# SMC_FrontPanel_ExtensionBoard_Step2_V14_.net
KiCad netlist of a schematic drawn in EAGLE
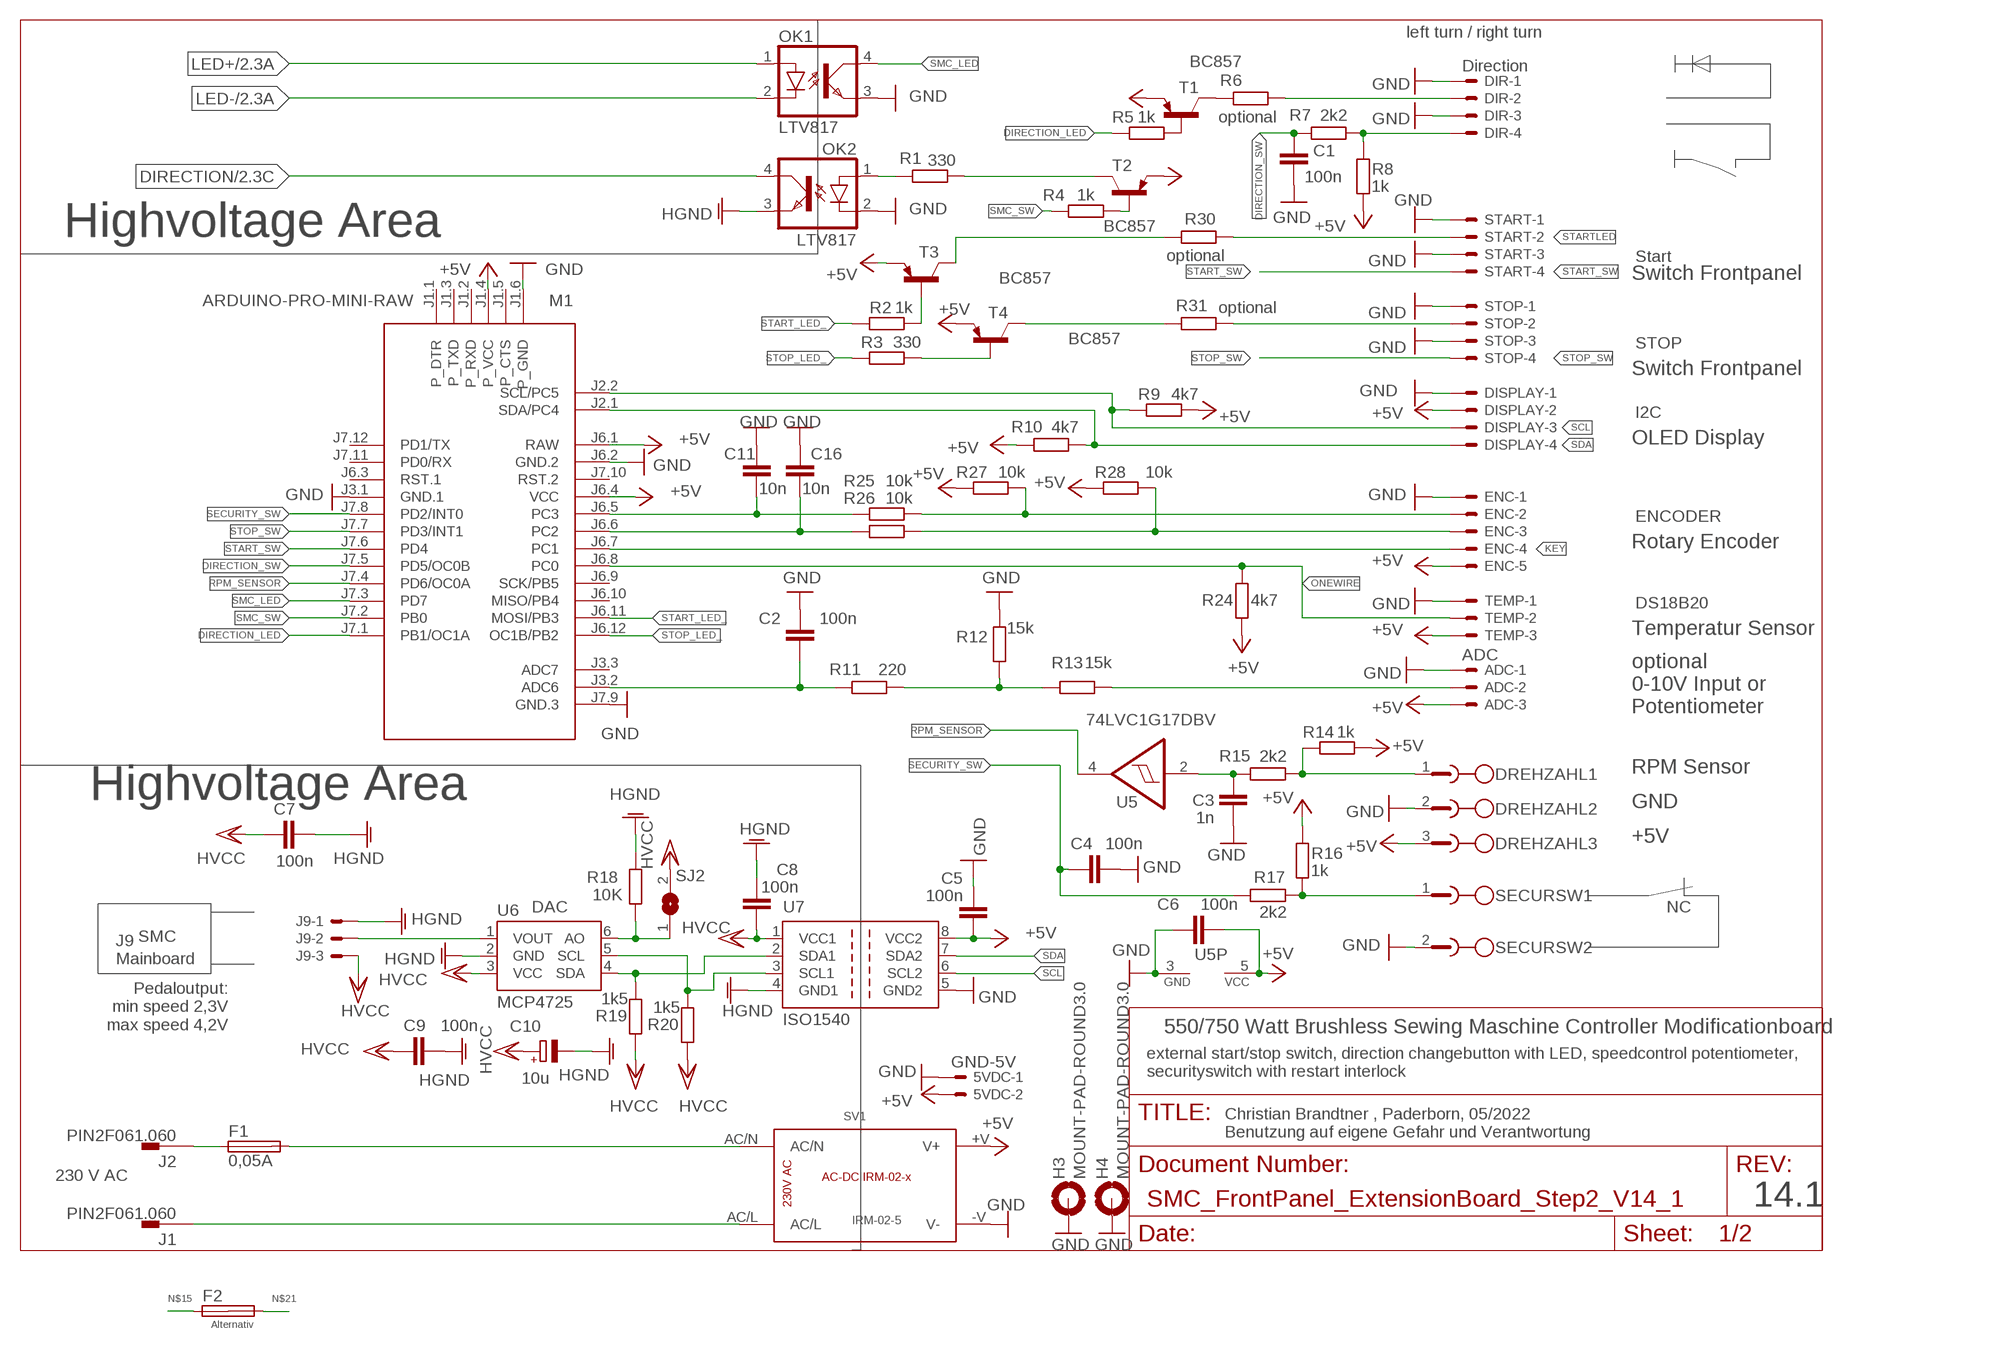
[diagram p0: schematic, sheet 1]
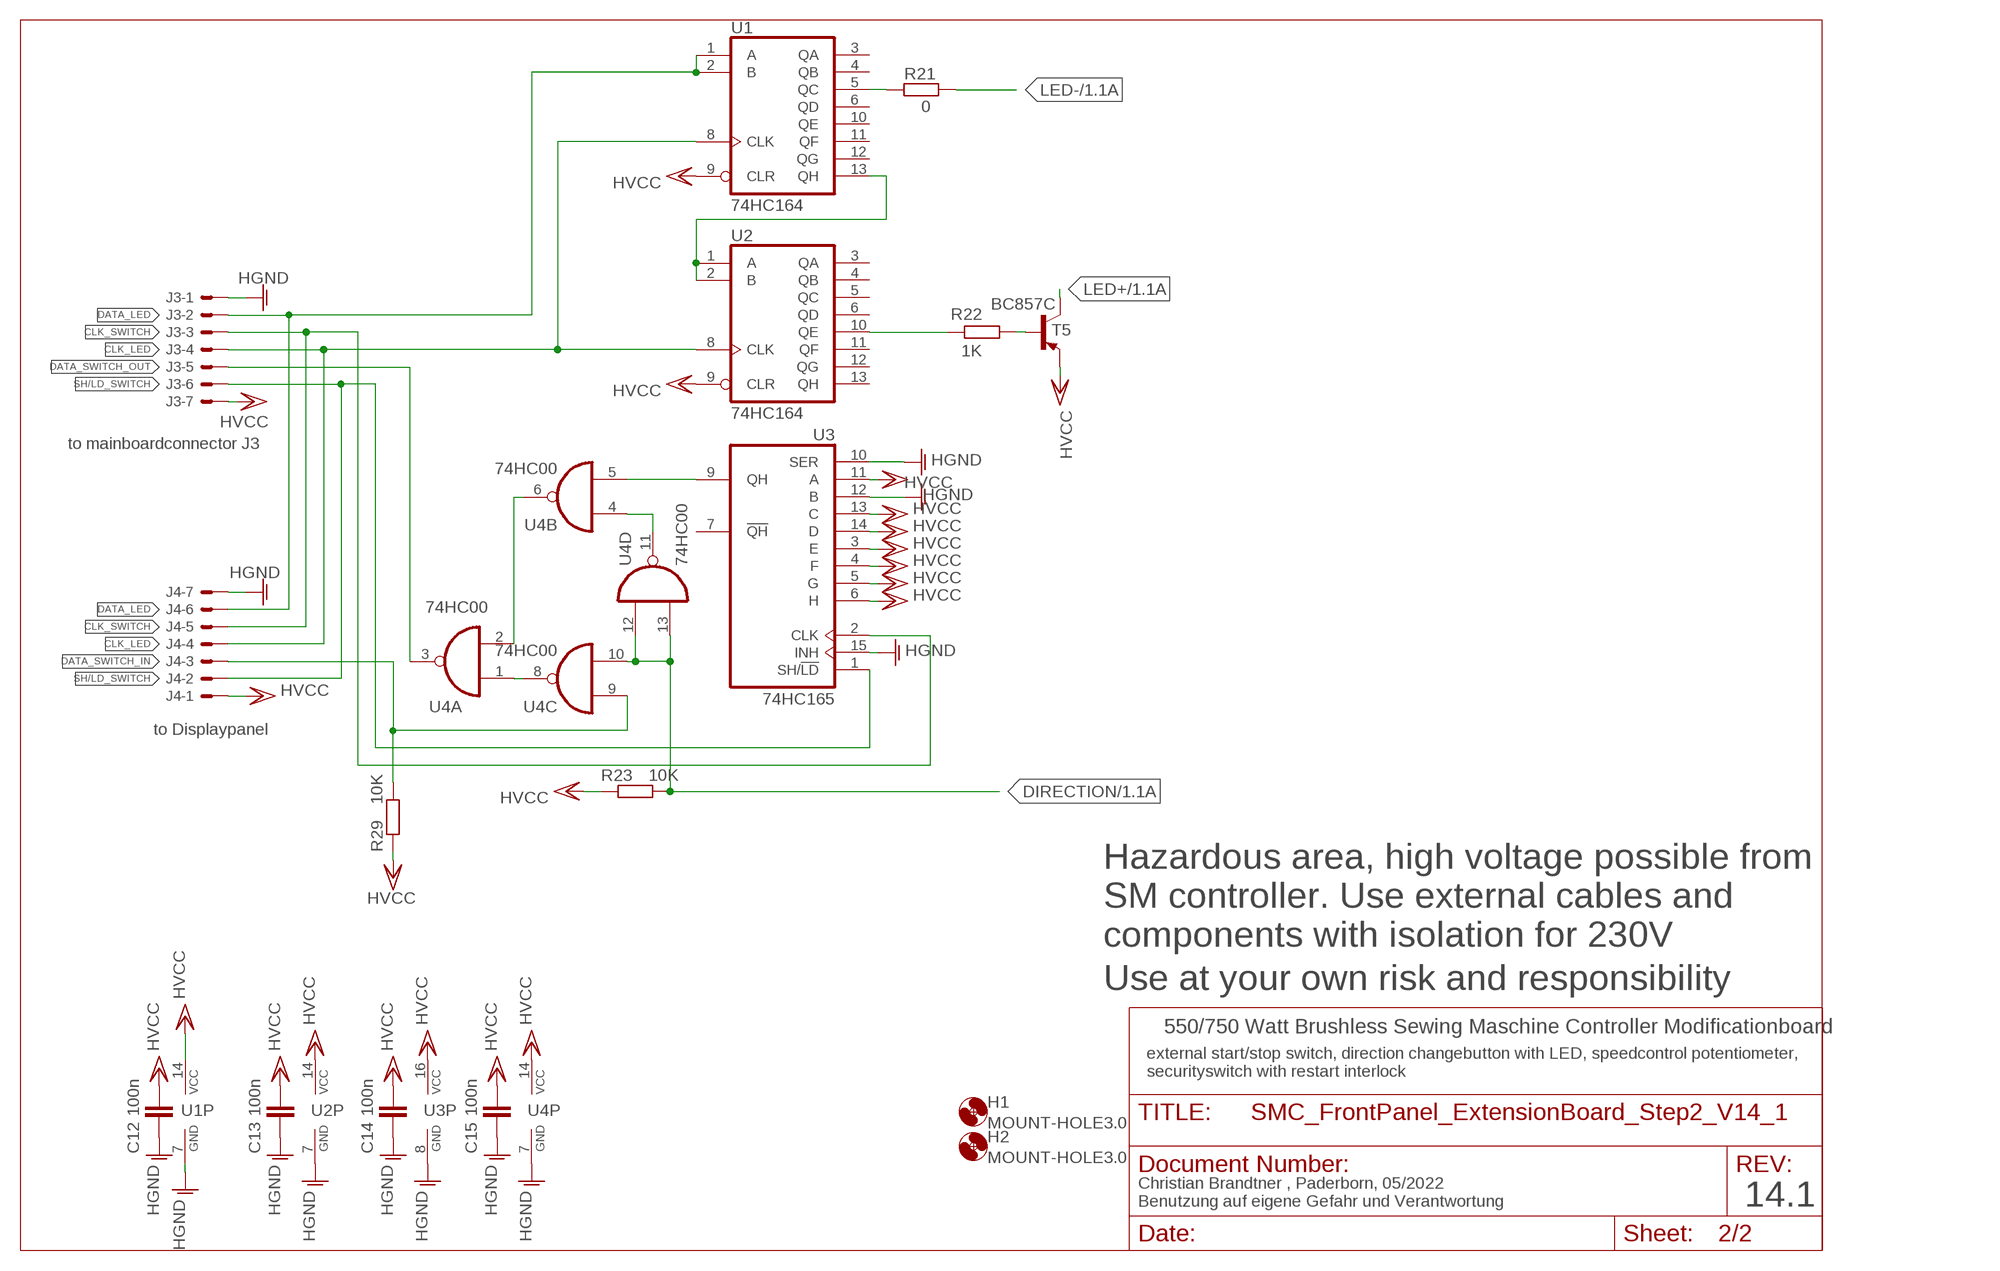
[diagram p1: schematic, sheet 2]

(export (version "E")
  (design (tool "Eeschema 10.0.6"))
  (components
    (comp (ref "5VDC")
      (value "GND-5V")
      (footprint "eagle-import:JST-XH-02-PACKAGE-ROUND-PAD")
      (libsource (lib "eagle-import") (part "JST-XH-02-PIN-ROUND-PAD"))
    )
    (comp (ref "ADC")
      (value "ADC")
      (footprint "eagle-import:JST-XH-03-PACKAGE-ROUND-PAD")
      (libsource (lib "eagle-import") (part "JST-XH-03-PIN-ROUND-PAD"))
    )
    (comp (ref "C1")
      (value "100n")
      (footprint "eagle-import:C0805")
      (libsource (lib "eagle-import") (part "C-EUC0805"))
    )
    (comp (ref "C2")
      (value "100n")
      (footprint "eagle-import:C0805")
      (libsource (lib "eagle-import") (part "C-EUC0805"))
    )
    (comp (ref "C3")
      (value "1n")
      (footprint "eagle-import:C0805")
      (libsource (lib "eagle-import") (part "C-EUC0805"))
    )
    (comp (ref "C4")
      (value "100n")
      (footprint "eagle-import:C0805")
      (libsource (lib "eagle-import") (part "C-EUC0805"))
    )
    (comp (ref "C5")
      (value "100n")
      (footprint "eagle-import:C0805")
      (libsource (lib "eagle-import") (part "C-EUC0805"))
    )
    (comp (ref "C6")
      (value "100n")
      (footprint "eagle-import:C0805")
      (libsource (lib "eagle-import") (part "C-EUC0805"))
    )
    (comp (ref "C7")
      (value "100n")
      (footprint "eagle-import:C0805")
      (libsource (lib "eagle-import") (part "C-EUC0805"))
    )
    (comp (ref "C8")
      (value "100n")
      (footprint "eagle-import:C0805")
      (libsource (lib "eagle-import") (part "C-EUC0805"))
    )
    (comp (ref "C9")
      (value "100n")
      (footprint "eagle-import:C0805")
      (libsource (lib "eagle-import") (part "C-EUC0805"))
    )
    (comp (ref "C10")
      (value "10u")
      (footprint "eagle-import:153CLV-0405")
      (libsource (lib "eagle-import") (part "CPOL-EU153CLV-0405"))
    )
    (comp (ref "C11")
      (value "10n")
      (footprint "eagle-import:C0805")
      (libsource (lib "eagle-import") (part "C-EUC0805"))
    )
    (comp (ref "C16")
      (value "10n")
      (footprint "eagle-import:C0805")
      (libsource (lib "eagle-import") (part "C-EUC0805"))
    )
    (comp (ref "DIR")
      (value "Direction")
      (footprint "eagle-import:JST-XH-04-PACKAGE-ROUND-PAD")
      (libsource (lib "eagle-import") (part "JST-XH-04-PIN-ROUND-PAD"))
    )
    (comp (ref "DISPLAY")
      (value "I2C")
      (footprint "eagle-import:JST-XH-04-PACKAGE-ROUND-PAD")
      (libsource (lib "eagle-import") (part "JST-XH-04-PIN-ROUND-PAD"))
    )
    (comp (ref "DREHZAHL")
      (value "MCV_1.5/3/-G-3.5")
      (footprint "eagle-import:1843619")
      (libsource (lib "eagle-import") (part "MCV_1.5/3/-G-3.5"))
    )
    (comp (ref "ENC")
      (value "ENCODER")
      (footprint "eagle-import:JST-XH-05-PACKAGE-ROUND-PAD")
      (libsource (lib "eagle-import") (part "JST-XH-05-PIN-ROUND-PAD"))
    )
    (comp (ref "F1")
      (value "0,05A")
      (footprint "eagle-import:MTA501100")
      (libsource (lib "eagle-import") (part "FUSE"))
    )
    (comp (ref "F2")
      (value "SHK20L")
      (footprint "eagle-import:SHK20L")
      (libsource (lib "eagle-import") (part "SHK20L"))
    )
    (comp (ref "H3")
      (value "MOUNT-PAD-ROUND3.0")
      (footprint "eagle-import:3,0-PAD")
      (libsource (lib "eagle-import") (part "MOUNT-PAD-ROUND3.0"))
    )
    (comp (ref "H4")
      (value "MOUNT-PAD-ROUND3.0")
      (footprint "eagle-import:3,0-PAD")
      (libsource (lib "eagle-import") (part "MOUNT-PAD-ROUND3.0"))
    )
    (comp (ref "J1")
      (value "PIN2F061.060")
      (footprint "eagle-import:F061.060")
      (libsource (lib "eagle-import") (part "PIN2F061.060"))
    )
    (comp (ref "J2")
      (value "PIN2F061.060")
      (footprint "eagle-import:F061.060")
      (libsource (lib "eagle-import") (part "PIN2F061.060"))
    )
    (comp (ref "J9")
      (value "JST-XH-03-PIN-ROUND-PAD")
      (footprint "eagle-import:JST-XH-03-PACKAGE-ROUND-PAD")
      (libsource (lib "eagle-import") (part "JST-XH-03-PIN-ROUND-PAD"))
    )
    (comp (ref "M1")
      (value "ARDUINO-PRO-MINI-RAW")
      (footprint "eagle-import:ARDUINO-PRO-MINI")
      (libsource (lib "eagle-import") (part "ARDUINO-PRO-MINI-RAW"))
    )
    (comp (ref "OK1")
      (value "LTV817")
      (footprint "eagle-import:SMD4-7")
      (fields (field (name "MF") "VISHAY/TELEFUNKEN") (field (name "MPN") "SFH6186-2"))
      (libsource (lib "eagle-import") (part "SFH618?6-2"))
    )
    (comp (ref "OK2")
      (value "LTV817")
      (footprint "eagle-import:SMD4-7")
      (fields (field (name "MF") "VISHAY/TELEFUNKEN") (field (name "MPN") "SFH6186-2"))
      (libsource (lib "eagle-import") (part "SFH618?6-2"))
    )
    (comp (ref "R1")
      (value "330")
      (footprint "eagle-import:R0805")
      (libsource (lib "eagle-import") (part "R-EU_R0805"))
    )
    (comp (ref "R2")
      (value "1k")
      (footprint "eagle-import:R0805")
      (libsource (lib "eagle-import") (part "R-EU_R0805"))
    )
    (comp (ref "R3")
      (value "330")
      (footprint "eagle-import:R0805")
      (libsource (lib "eagle-import") (part "R-EU_R0805"))
    )
    (comp (ref "R4")
      (value "1k")
      (footprint "eagle-import:R0805")
      (libsource (lib "eagle-import") (part "R-EU_R0805"))
    )
    (comp (ref "R5")
      (value "1k")
      (footprint "eagle-import:R0805")
      (libsource (lib "eagle-import") (part "R-EU_R0805"))
    )
    (comp (ref "R6")
      (value "optional")
      (footprint "eagle-import:R0805")
      (libsource (lib "eagle-import") (part "R-EU_R0805"))
    )
    (comp (ref "R7")
      (value "2k2")
      (footprint "eagle-import:R0805")
      (libsource (lib "eagle-import") (part "R-EU_R0805"))
    )
    (comp (ref "R8")
      (value "1k")
      (footprint "eagle-import:R0805")
      (libsource (lib "eagle-import") (part "R-EU_R0805"))
    )
    (comp (ref "R9")
      (value "4k7")
      (footprint "eagle-import:R0805")
      (libsource (lib "eagle-import") (part "R-EU_R0805"))
    )
    (comp (ref "R10")
      (value "4k7")
      (footprint "eagle-import:R0805")
      (libsource (lib "eagle-import") (part "R-EU_R0805"))
    )
    (comp (ref "R11")
      (value "220")
      (footprint "eagle-import:R0805")
      (libsource (lib "eagle-import") (part "R-EU_R0805"))
    )
    (comp (ref "R12")
      (value "15k")
      (footprint "eagle-import:R0805")
      (libsource (lib "eagle-import") (part "R-EU_R0805"))
    )
    (comp (ref "R13")
      (value "15k")
      (footprint "eagle-import:R0805")
      (libsource (lib "eagle-import") (part "R-EU_R0805"))
    )
    (comp (ref "R14")
      (value "1k")
      (footprint "eagle-import:R0805")
      (libsource (lib "eagle-import") (part "R-EU_R0805"))
    )
    (comp (ref "R15")
      (value "2k2")
      (footprint "eagle-import:R0805")
      (libsource (lib "eagle-import") (part "R-EU_R0805"))
    )
    (comp (ref "R16")
      (value "1k")
      (footprint "eagle-import:R0805")
      (libsource (lib "eagle-import") (part "R-EU_R0805"))
    )
    (comp (ref "R17")
      (value "2k2")
      (footprint "eagle-import:R0805")
      (libsource (lib "eagle-import") (part "R-EU_R0805"))
    )
    (comp (ref "R18")
      (value "10K")
      (footprint "eagle-import:R0805")
      (libsource (lib "eagle-import") (part "R-EU_R0805"))
    )
    (comp (ref "R19")
      (value "1k5")
      (footprint "eagle-import:R0805")
      (libsource (lib "eagle-import") (part "R-EU_R0805"))
    )
    (comp (ref "R20")
      (value "1k5")
      (footprint "eagle-import:R0805")
      (libsource (lib "eagle-import") (part "R-EU_R0805"))
    )
    (comp (ref "R24")
      (value "4k7")
      (footprint "eagle-import:R0805")
      (libsource (lib "eagle-import") (part "R-EU_R0805"))
    )
    (comp (ref "R25")
      (value "10k")
      (footprint "eagle-import:R0805")
      (libsource (lib "eagle-import") (part "R-EU_R0805"))
    )
    (comp (ref "R26")
      (value "10k")
      (footprint "eagle-import:R0805")
      (libsource (lib "eagle-import") (part "R-EU_R0805"))
    )
    (comp (ref "R27")
      (value "10k")
      (footprint "eagle-import:R0805")
      (libsource (lib "eagle-import") (part "R-EU_R0805"))
    )
    (comp (ref "R28")
      (value "10k")
      (footprint "eagle-import:R0805")
      (libsource (lib "eagle-import") (part "R-EU_R0805"))
    )
    (comp (ref "R30")
      (value "optional")
      (footprint "eagle-import:R0805")
      (libsource (lib "eagle-import") (part "R-EU_R0805"))
    )
    (comp (ref "R31")
      (value "optional")
      (footprint "eagle-import:R0805")
      (libsource (lib "eagle-import") (part "R-EU_R0805"))
    )
    (comp (ref "SECURSW")
      (value "MCV_1,5/2-G-3,5")
      (footprint "eagle-import:1843606")
      (libsource (lib "eagle-import") (part "MCV_1,5/2-G-3,5"))
    )
    (comp (ref "SJ2") (value "SJ") (footprint "eagle-import:SJ") (libsource (lib "eagle-import") (part "SJ")))
    (comp (ref "START")
      (value "Start")
      (footprint "eagle-import:JST-XH-04-PACKAGE-ROUND-PAD")
      (libsource (lib "eagle-import") (part "JST-XH-04-PIN-ROUND-PAD"))
    )
    (comp (ref "STOP")
      (value "STOP")
      (footprint "eagle-import:JST-XH-04-PACKAGE-ROUND-PAD")
      (libsource (lib "eagle-import") (part "JST-XH-04-PIN-ROUND-PAD"))
    )
    (comp (ref "SV1")
      (value "IRM-02-5")
      (footprint "eagle-import:IRM-02-X")
      (libsource (lib "eagle-import") (part "IRM-02-X"))
    )
    (comp (ref "T1")
      (value "BC857")
      (footprint "eagle-import:SOT23-BEC")
      (libsource (lib "eagle-import") (part "BC857SMDA"))
    )
    (comp (ref "T2")
      (value "BC857")
      (footprint "eagle-import:SOT23-BEC")
      (libsource (lib "eagle-import") (part "BC857SMDA"))
    )
    (comp (ref "T3")
      (value "BC857")
      (footprint "eagle-import:SOT23-BEC")
      (libsource (lib "eagle-import") (part "BC857SMDA"))
    )
    (comp (ref "T4")
      (value "BC857")
      (footprint "eagle-import:SOT23-BEC")
      (libsource (lib "eagle-import") (part "BC857SMDA"))
    )
    (comp (ref "TEMP")
      (value "DS18B20")
      (footprint "eagle-import:JST-XH-03-PACKAGE-ROUND-PAD")
      (libsource (lib "eagle-import") (part "JST-XH-03-PIN-ROUND-PAD"))
    )
    (comp (ref "U5")
      (value "74LVC1G17DBV")
      (footprint "eagle-import:SOT23-5")
      (libsource (lib "eagle-import") (part "741G17DBVLVC"))
    )
    (comp (ref "U6")
      (value "MCP4725")
      (footprint "eagle-import:SOT23-6")
      (libsource (lib "eagle-import") (part "MCP4725SOT-23"))
    )
    (comp (ref "U7")
      (value "ISO1540")
      (footprint "eagle-import:SO-08")
      (libsource (lib "eagle-import") (part "ISO1540"))
    )
    (comp (ref "C12")
      (value "100n")
      (footprint "eagle-import:C0805")
      (libsource (lib "eagle-import") (part "C-EUC0805"))
    )
    (comp (ref "C13")
      (value "100n")
      (footprint "eagle-import:C0805")
      (libsource (lib "eagle-import") (part "C-EUC0805"))
    )
    (comp (ref "C14")
      (value "100n")
      (footprint "eagle-import:C0805")
      (libsource (lib "eagle-import") (part "C-EUC0805"))
    )
    (comp (ref "C15")
      (value "100n")
      (footprint "eagle-import:C0805")
      (libsource (lib "eagle-import") (part "C-EUC0805"))
    )
    (comp (ref "H1")
      (value "MOUNT-HOLE3.0")
      (footprint "eagle-import:3,0")
      (libsource (lib "eagle-import") (part "MOUNT-HOLE3.0"))
    )
    (comp (ref "H2")
      (value "MOUNT-HOLE3.0")
      (footprint "eagle-import:3,0")
      (libsource (lib "eagle-import") (part "MOUNT-HOLE3.0"))
    )
    (comp (ref "J3")
      (value "to mainboardconnector J3")
      (footprint "eagle-import:JST-XH-07-PACKAGE-ROUND-PAD")
      (libsource (lib "eagle-import") (part "JST-XH-07-PIN-ROUND-PAD"))
    )
    (comp (ref "J4")
      (value "to Displaypanel")
      (footprint "eagle-import:JST-XH-07-PACKAGE-ROUND-PAD")
      (libsource (lib "eagle-import") (part "JST-XH-07-PIN-ROUND-PAD"))
    )
    (comp (ref "R21")
      (value "0")
      (footprint "eagle-import:R0805")
      (libsource (lib "eagle-import") (part "R-EU_R0805"))
    )
    (comp (ref "R22")
      (value "1K")
      (footprint "eagle-import:R0805")
      (libsource (lib "eagle-import") (part "R-EU_R0805"))
    )
    (comp (ref "R23")
      (value "10K")
      (footprint "eagle-import:R0805")
      (libsource (lib "eagle-import") (part "R-EU_R0805"))
    )
    (comp (ref "R29")
      (value "10K")
      (footprint "eagle-import:R0805")
      (libsource (lib "eagle-import") (part "R-EU_R0805"))
    )
    (comp (ref "T5")
      (value "BC857C")
      (footprint "eagle-import:SOT23-BEC")
      (libsource (lib "eagle-import") (part "-PNP-SOT23-BECBC857C"))
    )
    (comp (ref "U1")
      (value "74HC164")
      (footprint "eagle-import:SO14")
      (libsource (lib "eagle-import") (part "74164DHC"))
    )
    (comp (ref "U2")
      (value "74HC164")
      (footprint "eagle-import:SO14")
      (libsource (lib "eagle-import") (part "74164DHC"))
    )
    (comp (ref "U3")
      (value "74HC165")
      (footprint "eagle-import:SO16")
      (libsource (lib "eagle-import") (part "74165DHC"))
    )
    (comp (ref "U4")
      (value "74HC00")
      (footprint "eagle-import:SO14")
      (libsource (lib "eagle-import") (part "7400DHC"))
    )
  )
  (nets
    (net (code "1") (name "+5V") (class "Default")
      (node (ref "5VDC") (pin "2") (pinfunction "S_2") (pintype "passive"))
      (node (ref "ADC") (pin "3") (pinfunction "S_3") (pintype "passive"))
      (node (ref "C5") (pin "1") (pinfunction "1_1") (pintype "passive"))
      (node (ref "C6") (pin "1") (pinfunction "1_1") (pintype "passive"))
      (node (ref "DISPLAY") (pin "2") (pinfunction "S_2") (pintype "passive"))
      (node (ref "DREHZAHL") (pin "3") (pinfunction "1_3") (pintype "passive"))
      (node (ref "ENC") (pin "5") (pinfunction "S_5") (pintype "passive"))
      (node (ref "M1") (pin "J1.4") (pinfunction "P_VCC_J1.4") (pintype "bidirectional"))
      (node (ref "M1") (pin "J6.1") (pinfunction "RAW_J6.1") (pintype "power_in"))
      (node (ref "M1") (pin "J6.4") (pinfunction "VCC_J6.4") (pintype "power_in"))
      (node (ref "R10") (pin "1") (pinfunction "1_1") (pintype "passive"))
      (node (ref "R14") (pin "1") (pinfunction "1_1") (pintype "passive"))
      (node (ref "R16") (pin "1") (pinfunction "1_1") (pintype "passive"))
      (node (ref "R24") (pin "2") (pinfunction "2_2") (pintype "passive"))
      (node (ref "R27") (pin "1") (pinfunction "1_1") (pintype "passive"))
      (node (ref "R28") (pin "1") (pinfunction "1_1") (pintype "passive"))
      (node (ref "R8") (pin "2") (pinfunction "2_2") (pintype "passive"))
      (node (ref "R9") (pin "1") (pinfunction "1_1") (pintype "passive"))
      (node (ref "SV1") (pin "+V") (pinfunction "V+_+V") (pintype "bidirectional"))
      (node (ref "T1") (pin "E") (pinfunction "E_E") (pintype "passive"))
      (node (ref "T2") (pin "E") (pinfunction "E_E") (pintype "passive"))
      (node (ref "T3") (pin "E") (pinfunction "E_E") (pintype "passive"))
      (node (ref "T4") (pin "E") (pinfunction "E_E") (pintype "passive"))
      (node (ref "TEMP") (pin "3") (pinfunction "S_3") (pintype "passive"))
      (node (ref "U5") (pin "5") (pinfunction "VCC_5") (pintype "power_in"))
      (node (ref "U7") (pin "8") (pinfunction "VCC2_8") (pintype "power_in"))
    )
    (net (code "2") (name "CLK_LED") (class "Default")
      (node (ref "J3") (pin "4") (pinfunction "S_4") (pintype "passive"))
      (node (ref "J4") (pin "4") (pinfunction "S_4") (pintype "passive"))
      (node (ref "U1") (pin "8") (pinfunction "CLK_8") (pintype "input"))
      (node (ref "U2") (pin "8") (pinfunction "CLK_8") (pintype "input"))
    )
    (net (code "3") (name "CLK_SWITCH") (class "Default")
      (node (ref "J3") (pin "3") (pinfunction "S_3") (pintype "passive"))
      (node (ref "J4") (pin "5") (pinfunction "S_5") (pintype "passive"))
      (node (ref "U3") (pin "2") (pinfunction "CLK_2") (pintype "input"))
    )
    (net (code "4") (name "DATA_LED") (class "Default")
      (node (ref "J3") (pin "2") (pinfunction "S_2") (pintype "passive"))
      (node (ref "J4") (pin "6") (pinfunction "S_6") (pintype "passive"))
      (node (ref "U1") (pin "1") (pinfunction "A_1") (pintype "input"))
      (node (ref "U1") (pin "2") (pinfunction "B_2") (pintype "input"))
    )
    (net (code "5") (name "DATA_SWITCH_IN") (class "Default")
      (node (ref "J4") (pin "3") (pinfunction "S_3") (pintype "passive"))
      (node (ref "R29") (pin "1") (pinfunction "1_1") (pintype "passive"))
      (node (ref "U4") (pin "9") (pinfunction "I0_9") (pintype "input"))
    )
    (net (code "6") (name "DATA_SWITCH_OUT") (class "Default")
      (node (ref "J3") (pin "5") (pinfunction "S_5") (pintype "passive"))
      (node (ref "U4") (pin "3") (pinfunction "O_3") (pintype "output"))
    )
    (net (code "7") (name "DIRECTION") (class "Default")
      (node (ref "OK2") (pin "4") (pinfunction "COL_4") (pintype "passive"))
      (node (ref "R23") (pin "1") (pinfunction "1_1") (pintype "passive"))
      (node (ref "U4") (pin "10") (pinfunction "I1_10") (pintype "input"))
      (node (ref "U4") (pin "12") (pinfunction "I0_12") (pintype "input"))
      (node (ref "U4") (pin "13") (pinfunction "I1_13") (pintype "input"))
    )
    (net (code "8") (name "DIRECTION_LED") (class "Default")
      (node (ref "M1") (pin "J7.1") (pinfunction "PB1/OC1A_J7.1") (pintype "bidirectional"))
      (node (ref "R5") (pin "2") (pinfunction "2_2") (pintype "passive"))
    )
    (net (code "9") (name "DIRECTION_SW") (class "Default")
      (node (ref "C1") (pin "2") (pinfunction "2_2") (pintype "passive"))
      (node (ref "M1") (pin "J7.5") (pinfunction "PD5/OC0B_J7.5") (pintype "bidirectional"))
      (node (ref "R7") (pin "1") (pinfunction "1_1") (pintype "passive"))
    )
    (net (code "10") (name "GND") (class "Default")
      (node (ref "5VDC") (pin "1") (pinfunction "S_1") (pintype "passive"))
      (node (ref "ADC") (pin "1") (pinfunction "S_1") (pintype "passive"))
      (node (ref "C1") (pin "1") (pinfunction "1_1") (pintype "passive"))
      (node (ref "C11") (pin "2") (pinfunction "2_2") (pintype "passive"))
      (node (ref "C16") (pin "2") (pinfunction "2_2") (pintype "passive"))
      (node (ref "C2") (pin "2") (pinfunction "2_2") (pintype "passive"))
      (node (ref "C3") (pin "1") (pinfunction "1_1") (pintype "passive"))
      (node (ref "C4") (pin "2") (pinfunction "2_2") (pintype "passive"))
      (node (ref "C5") (pin "2") (pinfunction "2_2") (pintype "passive"))
      (node (ref "C6") (pin "2") (pinfunction "2_2") (pintype "passive"))
      (node (ref "DIR") (pin "1") (pinfunction "S_1") (pintype "passive"))
      (node (ref "DIR") (pin "3") (pinfunction "S_3") (pintype "passive"))
      (node (ref "DISPLAY") (pin "1") (pinfunction "S_1") (pintype "passive"))
      (node (ref "DREHZAHL") (pin "2") (pinfunction "1_2") (pintype "passive"))
      (node (ref "ENC") (pin "1") (pinfunction "S_1") (pintype "passive"))
      (node (ref "H3") (pin "B3,0") (pinfunction "MOUNT_B3,0") (pintype "passive"))
      (node (ref "H4") (pin "B3,0") (pinfunction "MOUNT_B3,0") (pintype "passive"))
      (node (ref "M1") (pin "J1.6") (pinfunction "P_GND_J1.6") (pintype "bidirectional"))
      (node (ref "M1") (pin "J3.1") (pinfunction "GND.1_J3.1") (pintype "power_in"))
      (node (ref "M1") (pin "J6.2") (pinfunction "GND.2_J6.2") (pintype "power_in"))
      (node (ref "M1") (pin "J7.9") (pinfunction "GND.3_J7.9") (pintype "bidirectional"))
      (node (ref "OK1") (pin "3") (pinfunction "EMIT_3") (pintype "passive"))
      (node (ref "OK2") (pin "2") (pinfunction "C_2") (pintype "passive"))
      (node (ref "R12") (pin "2") (pinfunction "2_2") (pintype "passive"))
      (node (ref "SECURSW") (pin "2") (pinfunction "1_2") (pintype "passive"))
      (node (ref "START") (pin "1") (pinfunction "S_1") (pintype "passive"))
      (node (ref "START") (pin "3") (pinfunction "S_3") (pintype "passive"))
      (node (ref "STOP") (pin "1") (pinfunction "S_1") (pintype "passive"))
      (node (ref "STOP") (pin "3") (pinfunction "S_3") (pintype "passive"))
      (node (ref "SV1") (pin "-V") (pinfunction "V-_-V") (pintype "bidirectional"))
      (node (ref "TEMP") (pin "1") (pinfunction "S_1") (pintype "passive"))
      (node (ref "U5") (pin "3") (pinfunction "GND_3") (pintype "power_in"))
      (node (ref "U7") (pin "5") (pinfunction "GND2_5") (pintype "power_in"))
    )
    (net (code "11") (name "HGND") (class "Default")
      (node (ref "C10") (pin "-") (pinfunction "-_-") (pintype "passive"))
      (node (ref "C12") (pin "1") (pinfunction "1_1") (pintype "passive"))
      (node (ref "C13") (pin "1") (pinfunction "1_1") (pintype "passive"))
      (node (ref "C14") (pin "1") (pinfunction "1_1") (pintype "passive"))
      (node (ref "C15") (pin "1") (pinfunction "1_1") (pintype "passive"))
      (node (ref "C7") (pin "1") (pinfunction "1_1") (pintype "passive"))
      (node (ref "C8") (pin "2") (pinfunction "2_2") (pintype "passive"))
      (node (ref "C9") (pin "1") (pinfunction "1_1") (pintype "passive"))
      (node (ref "J3") (pin "1") (pinfunction "S_1") (pintype "passive"))
      (node (ref "J4") (pin "7") (pinfunction "S_7") (pintype "passive"))
      (node (ref "J9") (pin "1") (pinfunction "S_1") (pintype "passive"))
      (node (ref "OK2") (pin "3") (pinfunction "EMIT_3") (pintype "passive"))
      (node (ref "R18") (pin "1") (pinfunction "1_1") (pintype "passive"))
      (node (ref "U1") (pin "7") (pinfunction "GND_7") (pintype "power_in"))
      (node (ref "U2") (pin "7") (pinfunction "GND_7") (pintype "power_in"))
      (node (ref "U3") (pin "10") (pinfunction "SER_10") (pintype "input"))
      (node (ref "U3") (pin "12") (pinfunction "B_12") (pintype "input"))
      (node (ref "U3") (pin "15") (pinfunction "INH_15") (pintype "input"))
      (node (ref "U3") (pin "8") (pinfunction "GND_8") (pintype "power_in"))
      (node (ref "U4") (pin "7") (pinfunction "GND_7") (pintype "power_in"))
      (node (ref "U6") (pin "2") (pinfunction "GND_2") (pintype "bidirectional"))
      (node (ref "U7") (pin "4") (pinfunction "GND1_4") (pintype "power_in"))
    )
    (net (code "12") (name "HVCC") (class "Default")
      (node (ref "C10") (pin "+") (pinfunction "+_+") (pintype "passive"))
      (node (ref "C12") (pin "2") (pinfunction "2_2") (pintype "passive"))
      (node (ref "C13") (pin "2") (pinfunction "2_2") (pintype "passive"))
      (node (ref "C14") (pin "2") (pinfunction "2_2") (pintype "passive"))
      (node (ref "C15") (pin "2") (pinfunction "2_2") (pintype "passive"))
      (node (ref "C7") (pin "2") (pinfunction "2_2") (pintype "passive"))
      (node (ref "C8") (pin "1") (pinfunction "1_1") (pintype "passive"))
      (node (ref "C9") (pin "2") (pinfunction "2_2") (pintype "passive"))
      (node (ref "J3") (pin "7") (pinfunction "S_7") (pintype "passive"))
      (node (ref "J4") (pin "1") (pinfunction "S_1") (pintype "passive"))
      (node (ref "J9") (pin "3") (pinfunction "S_3") (pintype "passive"))
      (node (ref "R19") (pin "2") (pinfunction "2_2") (pintype "passive"))
      (node (ref "R20") (pin "2") (pinfunction "2_2") (pintype "passive"))
      (node (ref "R23") (pin "2") (pinfunction "2_2") (pintype "passive"))
      (node (ref "R29") (pin "2") (pinfunction "2_2") (pintype "passive"))
      (node (ref "SJ2") (pin "2") (pinfunction "2_2") (pintype "passive"))
      (node (ref "T5") (pin "E") (pinfunction "E_E") (pintype "passive"))
      (node (ref "U1") (pin "14") (pinfunction "VCC_14") (pintype "power_in"))
      (node (ref "U1") (pin "9") (pinfunction "CLR_9") (pintype "input"))
      (node (ref "U2") (pin "14") (pinfunction "VCC_14") (pintype "power_in"))
      (node (ref "U2") (pin "9") (pinfunction "CLR_9") (pintype "input"))
      (node (ref "U3") (pin "11") (pinfunction "A_11") (pintype "input"))
      (node (ref "U3") (pin "13") (pinfunction "C_13") (pintype "input"))
      (node (ref "U3") (pin "14") (pinfunction "D_14") (pintype "input"))
      (node (ref "U3") (pin "16") (pinfunction "VCC_16") (pintype "power_in"))
      (node (ref "U3") (pin "3") (pinfunction "E_3") (pintype "input"))
      (node (ref "U3") (pin "4") (pinfunction "F_4") (pintype "input"))
      (node (ref "U3") (pin "5") (pinfunction "G_5") (pintype "input"))
      (node (ref "U3") (pin "6") (pinfunction "H_6") (pintype "input"))
      (node (ref "U4") (pin "14") (pinfunction "VCC_14") (pintype "power_in"))
      (node (ref "U6") (pin "3") (pinfunction "VCC_3") (pintype "bidirectional"))
      (node (ref "U7") (pin "1") (pinfunction "VCC1_1") (pintype "power_in"))
    )
    (net (code "13") (name "KEY") (class "Default")
      (node (ref "ENC") (pin "4") (pinfunction "S_4") (pintype "passive"))
      (node (ref "M1") (pin "J6.7") (pinfunction "PC1_J6.7") (pintype "bidirectional"))
    )
    (net (code "14") (name "LED+") (class "Default")
      (node (ref "OK1") (pin "1") (pinfunction "A_1") (pintype "passive"))
      (node (ref "T5") (pin "C") (pinfunction "C_C") (pintype "passive"))
    )
    (net (code "15") (name "LED-") (class "Default")
      (node (ref "OK1") (pin "2") (pinfunction "C_2") (pintype "passive"))
      (node (ref "R21") (pin "2") (pinfunction "2_2") (pintype "passive"))
    )
    (net (code "16") (name "N$15") (class "Default")
      (node (ref "F1") (pin "1") (pinfunction "1_1") (pintype "passive"))
      (node (ref "F2") (pin "1A") (pinfunction "1A_1A") (pintype "passive"))
      (node (ref "J2") (pin "A1") (pinfunction "1_A1") (pintype "passive"))
      (node (ref "J2") (pin "A2") (pinfunction "1_A2") (pintype "passive"))
    )
    (net (code "17") (name "N$21") (class "Default")
      (node (ref "F1") (pin "2") (pinfunction "2_2") (pintype "passive"))
      (node (ref "F2") (pin "2A") (pinfunction "2A_2A") (pintype "passive"))
      (node (ref "SV1") (pin "AC/N") (pinfunction "AC/N_AC/N") (pintype "bidirectional"))
    )
    (net (code "18") (name "Net-(ADCB-S)") (class "Default")
      (node (ref "ADC") (pin "2") (pinfunction "S_2") (pintype "passive"))
      (node (ref "R13") (pin "1") (pinfunction "1_1") (pintype "passive"))
    )
    (net (code "19") (name "Net-(DIRB-S)") (class "Default")
      (node (ref "DIR") (pin "2") (pinfunction "S_2") (pintype "passive"))
      (node (ref "R6") (pin "1") (pinfunction "1_1") (pintype "passive"))
    )
    (net (code "20") (name "Net-(DIRD-S)") (class "Default")
      (node (ref "DIR") (pin "4") (pinfunction "S_4") (pintype "passive"))
      (node (ref "R7") (pin "2") (pinfunction "2_2") (pintype "passive"))
      (node (ref "R8") (pin "1") (pinfunction "1_1") (pintype "passive"))
    )
    (net (code "21") (name "Net-(DREHZAHL-Pad1)") (class "Default")
      (node (ref "DREHZAHL") (pin "1") (pinfunction "1_1") (pintype "passive"))
      (node (ref "R14") (pin "2") (pinfunction "2_2") (pintype "passive"))
      (node (ref "R15") (pin "2") (pinfunction "2_2") (pintype "passive"))
    )
    (net (code "22") (name "Net-(ENCB-S)") (class "Default")
      (node (ref "ENC") (pin "2") (pinfunction "S_2") (pintype "passive"))
      (node (ref "R25") (pin "2") (pinfunction "2_2") (pintype "passive"))
      (node (ref "R27") (pin "2") (pinfunction "2_2") (pintype "passive"))
    )
    (net (code "23") (name "Net-(ENCC-S)") (class "Default")
      (node (ref "ENC") (pin "3") (pinfunction "S_3") (pintype "passive"))
      (node (ref "R26") (pin "2") (pinfunction "2_2") (pintype "passive"))
      (node (ref "R28") (pin "2") (pinfunction "2_2") (pintype "passive"))
    )
    (net (code "24") (name "Net-(J1-1-PadA1)") (class "Default")
      (node (ref "J1") (pin "A1") (pinfunction "1_A1") (pintype "passive"))
      (node (ref "J1") (pin "A2") (pinfunction "1_A2") (pintype "passive"))
      (node (ref "SV1") (pin "AC/L") (pinfunction "AC/L_AC/L") (pintype "bidirectional"))
    )
    (net (code "25") (name "Net-(J9B-S)") (class "Default")
      (node (ref "J9") (pin "2") (pinfunction "S_2") (pintype "passive"))
      (node (ref "U6") (pin "1") (pinfunction "VOUT_1") (pintype "bidirectional"))
    )
    (net (code "26") (name "Net-(M1-ADC6)") (class "Default")
      (node (ref "C2") (pin "1") (pinfunction "1_1") (pintype "passive"))
      (node (ref "M1") (pin "J3.2") (pinfunction "ADC6_J3.2") (pintype "bidirectional"))
      (node (ref "R11") (pin "1") (pinfunction "1_1") (pintype "passive"))
    )
    (net (code "27") (name "Net-(M1-PC2)") (class "Default")
      (node (ref "C16") (pin "1") (pinfunction "1_1") (pintype "passive"))
      (node (ref "M1") (pin "J6.6") (pinfunction "PC2_J6.6") (pintype "bidirectional"))
      (node (ref "R26") (pin "1") (pinfunction "1_1") (pintype "passive"))
    )
    (net (code "28") (name "Net-(M1-PC3)") (class "Default")
      (node (ref "C11") (pin "1") (pinfunction "1_1") (pintype "passive"))
      (node (ref "M1") (pin "J6.5") (pinfunction "PC3_J6.5") (pintype "bidirectional"))
      (node (ref "R25") (pin "1") (pinfunction "1_1") (pintype "passive"))
    )
    (net (code "29") (name "Net-(OK2-A)") (class "Default")
      (node (ref "OK2") (pin "1") (pinfunction "A_1") (pintype "passive"))
      (node (ref "R1") (pin "2") (pinfunction "2_2") (pintype "passive"))
    )
    (net (code "30") (name "Net-(R1-Pad1)") (class "Default")
      (node (ref "R1") (pin "1") (pinfunction "1_1") (pintype "passive"))
      (node (ref "T2") (pin "C") (pinfunction "C_C") (pintype "passive"))
    )
    (net (code "31") (name "Net-(R2-Pad1)") (class "Default")
      (node (ref "R2") (pin "1") (pinfunction "1_1") (pintype "passive"))
      (node (ref "T3") (pin "B") (pinfunction "B_B") (pintype "passive"))
    )
    (net (code "32") (name "Net-(R3-Pad1)") (class "Default")
      (node (ref "R3") (pin "1") (pinfunction "1_1") (pintype "passive"))
      (node (ref "T4") (pin "B") (pinfunction "B_B") (pintype "passive"))
    )
    (net (code "33") (name "Net-(R4-Pad1)") (class "Default")
      (node (ref "R4") (pin "1") (pinfunction "1_1") (pintype "passive"))
      (node (ref "T2") (pin "B") (pinfunction "B_B") (pintype "passive"))
    )
    (net (code "34") (name "Net-(R5-Pad1)") (class "Default")
      (node (ref "R5") (pin "1") (pinfunction "1_1") (pintype "passive"))
      (node (ref "T1") (pin "B") (pinfunction "B_B") (pintype "passive"))
    )
    (net (code "35") (name "Net-(R6-Pad2)") (class "Default")
      (node (ref "R6") (pin "2") (pinfunction "2_2") (pintype "passive"))
      (node (ref "T1") (pin "C") (pinfunction "C_C") (pintype "passive"))
    )
    (net (code "36") (name "Net-(R11-Pad2)") (class "Default")
      (node (ref "R11") (pin "2") (pinfunction "2_2") (pintype "passive"))
      (node (ref "R12") (pin "1") (pinfunction "1_1") (pintype "passive"))
      (node (ref "R13") (pin "2") (pinfunction "2_2") (pintype "passive"))
    )
    (net (code "37") (name "Net-(R16-Pad2)") (class "Default")
      (node (ref "R16") (pin "2") (pinfunction "2_2") (pintype "passive"))
      (node (ref "R17") (pin "2") (pinfunction "2_2") (pintype "passive"))
      (node (ref "SECURSW") (pin "1") (pinfunction "1_1") (pintype "passive"))
    )
    (net (code "38") (name "Net-(R22-Pad1)") (class "Default")
      (node (ref "R22") (pin "1") (pinfunction "1_1") (pintype "passive"))
      (node (ref "T5") (pin "B") (pinfunction "B_B") (pintype "passive"))
    )
    (net (code "39") (name "Net-(R31-Pad2)") (class "Default")
      (node (ref "R31") (pin "2") (pinfunction "2_2") (pintype "passive"))
      (node (ref "T4") (pin "C") (pinfunction "C_C") (pintype "passive"))
    )
    (net (code "40") (name "Net-(STARTB-S)") (class "Default")
      (node (ref "R30") (pin "1") (pinfunction "1_1") (pintype "passive"))
      (node (ref "START") (pin "2") (pinfunction "S_2") (pintype "passive"))
    )
    (net (code "41") (name "Net-(STOPB-S)") (class "Default")
      (node (ref "R31") (pin "1") (pinfunction "1_1") (pintype "passive"))
      (node (ref "STOP") (pin "2") (pinfunction "S_2") (pintype "passive"))
    )
    (net (code "42") (name "Net-(U1A-QC)") (class "Default")
      (node (ref "R21") (pin "1") (pinfunction "1_1") (pintype "passive"))
      (node (ref "U1") (pin "5") (pinfunction "QC_5") (pintype "output"))
    )
    (net (code "43") (name "Net-(U1A-QH)") (class "Default")
      (node (ref "U1") (pin "13") (pinfunction "QH_13") (pintype "output"))
      (node (ref "U2") (pin "1") (pinfunction "A_1") (pintype "input"))
      (node (ref "U2") (pin "2") (pinfunction "B_2") (pintype "input"))
    )
    (net (code "44") (name "Net-(U2A-QE)") (class "Default")
      (node (ref "R22") (pin "2") (pinfunction "2_2") (pintype "passive"))
      (node (ref "U2") (pin "10") (pinfunction "QE_10") (pintype "output"))
    )
    (net (code "45") (name "Net-(U3A-QH)") (class "Default")
      (node (ref "U3") (pin "9") (pinfunction "QH_9") (pintype "output"))
      (node (ref "U4") (pin "5") (pinfunction "I1_5") (pintype "input"))
    )
    (net (code "46") (name "Net-(U4A-I0)") (class "Default")
      (node (ref "U4") (pin "1") (pinfunction "I0_1") (pintype "input"))
      (node (ref "U4") (pin "8") (pinfunction "O_8") (pintype "output"))
    )
    (net (code "47") (name "Net-(U4A-I1)") (class "Default")
      (node (ref "U4") (pin "2") (pinfunction "I1_2") (pintype "input"))
      (node (ref "U4") (pin "6") (pinfunction "O_6") (pintype "output"))
    )
    (net (code "48") (name "Net-(U4B-I0)") (class "Default")
      (node (ref "U4") (pin "11") (pinfunction "O_11") (pintype "output"))
      (node (ref "U4") (pin "4") (pinfunction "I0_4") (pintype "input"))
    )
    (net (code "49") (name "Net-(U5A-I)") (class "Default")
      (node (ref "C3") (pin "2") (pinfunction "2_2") (pintype "passive"))
      (node (ref "R15") (pin "1") (pinfunction "1_1") (pintype "passive"))
      (node (ref "U5") (pin "2") (pinfunction "I_2") (pintype "input"))
    )
    (net (code "50") (name "Net-(U6-AO)") (class "Default")
      (node (ref "R18") (pin "2") (pinfunction "2_2") (pintype "passive"))
      (node (ref "SJ2") (pin "1") (pinfunction "1_1") (pintype "passive"))
      (node (ref "U6") (pin "6") (pinfunction "AO_6") (pintype "bidirectional"))
    )
    (net (code "51") (name "Net-(U6-SCL)") (class "Default")
      (node (ref "R20") (pin "1") (pinfunction "1_1") (pintype "passive"))
      (node (ref "U6") (pin "5") (pinfunction "SCL_5") (pintype "bidirectional"))
      (node (ref "U7") (pin "3") (pinfunction "SCL1_3") (pintype "input"))
    )
    (net (code "52") (name "Net-(U6-SDA)") (class "Default")
      (node (ref "R19") (pin "1") (pinfunction "1_1") (pintype "passive"))
      (node (ref "U6") (pin "4") (pinfunction "SDA_4") (pintype "bidirectional"))
      (node (ref "U7") (pin "2") (pinfunction "SDA1_2") (pintype "input"))
    )
    (net (code "53") (name "ONEWIRE") (class "Default")
      (node (ref "M1") (pin "J6.8") (pinfunction "PC0_J6.8") (pintype "bidirectional"))
      (node (ref "R24") (pin "1") (pinfunction "1_1") (pintype "passive"))
      (node (ref "TEMP") (pin "2") (pinfunction "S_2") (pintype "passive"))
    )
    (net (code "54") (name "RPM_SENSOR") (class "Default")
      (node (ref "M1") (pin "J7.4") (pinfunction "PD6/OC0A_J7.4") (pintype "bidirectional"))
      (node (ref "U5") (pin "4") (pinfunction "O_4") (pintype "output"))
    )
    (net (code "55") (name "SCL") (class "Default")
      (node (ref "DISPLAY") (pin "3") (pinfunction "S_3") (pintype "passive"))
      (node (ref "M1") (pin "J2.2") (pinfunction "SCL/PC5_J2.2") (pintype "bidirectional"))
      (node (ref "R9") (pin "2") (pinfunction "2_2") (pintype "passive"))
      (node (ref "U7") (pin "6") (pinfunction "SCL2_6") (pintype "output"))
    )
    (net (code "56") (name "SDA") (class "Default")
      (node (ref "DISPLAY") (pin "4") (pinfunction "S_4") (pintype "passive"))
      (node (ref "M1") (pin "J2.1") (pinfunction "SDA/PC4_J2.1") (pintype "bidirectional"))
      (node (ref "R10") (pin "2") (pinfunction "2_2") (pintype "passive"))
      (node (ref "U7") (pin "7") (pinfunction "SDA2_7") (pintype "output"))
    )
    (net (code "57") (name "SECURITY_SW") (class "Default")
      (node (ref "C4") (pin "1") (pinfunction "1_1") (pintype "passive"))
      (node (ref "M1") (pin "J7.8") (pinfunction "PD2/INT0_J7.8") (pintype "bidirectional"))
      (node (ref "R17") (pin "1") (pinfunction "1_1") (pintype "passive"))
    )
    (net (code "58") (name "SH{slash}LD_SWITCH") (class "Default")
      (node (ref "J3") (pin "6") (pinfunction "S_6") (pintype "passive"))
      (node (ref "J4") (pin "2") (pinfunction "S_2") (pintype "passive"))
      (node (ref "U3") (pin "1") (pinfunction "SH/~{LD}_1") (pintype "input"))
    )
    (net (code "59") (name "SMC_LED") (class "Default")
      (node (ref "M1") (pin "J7.3") (pinfunction "PD7_J7.3") (pintype "bidirectional"))
      (node (ref "OK1") (pin "4") (pinfunction "COL_4") (pintype "passive"))
    )
    (net (code "60") (name "SMC_SW") (class "Default")
      (node (ref "M1") (pin "J7.2") (pinfunction "PB0_J7.2") (pintype "bidirectional"))
      (node (ref "R4") (pin "2") (pinfunction "2_2") (pintype "passive"))
    )
    (net (code "61") (name "STARTLED") (class "Default")
      (node (ref "R30") (pin "2") (pinfunction "2_2") (pintype "passive"))
      (node (ref "T3") (pin "C") (pinfunction "C_C") (pintype "passive"))
    )
    (net (code "62") (name "START_LED_") (class "Default")
      (node (ref "M1") (pin "J6.11") (pinfunction "MOSI/PB3_J6.11") (pintype "bidirectional"))
      (node (ref "R2") (pin "2") (pinfunction "2_2") (pintype "passive"))
    )
    (net (code "63") (name "START_SW") (class "Default")
      (node (ref "M1") (pin "J7.6") (pinfunction "PD4_J7.6") (pintype "bidirectional"))
      (node (ref "START") (pin "4") (pinfunction "S_4") (pintype "passive"))
    )
    (net (code "64") (name "STOP_LED_") (class "Default")
      (node (ref "M1") (pin "J6.12") (pinfunction "OC1B/PB2_J6.12") (pintype "bidirectional"))
      (node (ref "R3") (pin "2") (pinfunction "2_2") (pintype "passive"))
    )
    (net (code "65") (name "STOP_SW") (class "Default")
      (node (ref "M1") (pin "J7.7") (pinfunction "PD3/INT1_J7.7") (pintype "bidirectional"))
      (node (ref "STOP") (pin "4") (pinfunction "S_4") (pintype "passive"))
    )
    (net (code "66") (name "unconnected-(F2-Pad1B)") (class "Default")
      (node (ref "F2") (pin "1B") (pinfunction "1B_1B") (pintype "passive"))
    )
    (net (code "67") (name "unconnected-(F2-Pad2B)") (class "Default")
      (node (ref "F2") (pin "2B") (pinfunction "2B_2B") (pintype "passive"))
    )
    (net (code "68") (name "unconnected-(M1-ADC7-PadJ3.3)") (class "Default")
      (node (ref "M1") (pin "J3.3") (pinfunction "ADC7_J3.3") (pintype "bidirectional"))
    )
    (net (code "69") (name "unconnected-(M1-MISO{slash}PB4-PadJ6.10)") (class "Default")
      (node (ref "M1") (pin "J6.10") (pinfunction "MISO/PB4_J6.10") (pintype "bidirectional"))
    )
    (net (code "70") (name "unconnected-(M1-PD0{slash}RX-PadJ7.11)") (class "Default")
      (node (ref "M1") (pin "J7.11") (pinfunction "PD0/RX_J7.11") (pintype "bidirectional"))
    )
    (net (code "71") (name "unconnected-(M1-PD1{slash}TX-PadJ7.12)") (class "Default")
      (node (ref "M1") (pin "J7.12") (pinfunction "PD1/TX_J7.12") (pintype "bidirectional"))
    )
    (net (code "72") (name "unconnected-(M1-P_CTS-PadJ1.5)") (class "Default")
      (node (ref "M1") (pin "J1.5") (pinfunction "P_CTS_J1.5") (pintype "bidirectional"))
    )
    (net (code "73") (name "unconnected-(M1-P_DTR-PadJ1.1)") (class "Default")
      (node (ref "M1") (pin "J1.1") (pinfunction "P_DTR_J1.1") (pintype "bidirectional"))
    )
    (net (code "74") (name "unconnected-(M1-P_RXD-PadJ1.2)") (class "Default")
      (node (ref "M1") (pin "J1.2") (pinfunction "P_RXD_J1.2") (pintype "bidirectional"))
    )
    (net (code "75") (name "unconnected-(M1-P_TXD-PadJ1.3)") (class "Default")
      (node (ref "M1") (pin "J1.3") (pinfunction "P_TXD_J1.3") (pintype "bidirectional"))
    )
    (net (code "76") (name "unconnected-(M1-RST.1-PadJ6.3)") (class "Default")
      (node (ref "M1") (pin "J6.3") (pinfunction "RST.1_J6.3") (pintype "bidirectional"))
    )
    (net (code "77") (name "unconnected-(M1-RST.2-PadJ7.10)") (class "Default")
      (node (ref "M1") (pin "J7.10") (pinfunction "RST.2_J7.10") (pintype "bidirectional"))
    )
    (net (code "78") (name "unconnected-(M1-SCK{slash}PB5-PadJ6.9)") (class "Default")
      (node (ref "M1") (pin "J6.9") (pinfunction "SCK/PB5_J6.9") (pintype "bidirectional"))
    )
    (net (code "79") (name "unconnected-(U1A-QA-Pad3)") (class "Default")
      (node (ref "U1") (pin "3") (pinfunction "QA_3") (pintype "output"))
    )
    (net (code "80") (name "unconnected-(U1A-QB-Pad4)") (class "Default")
      (node (ref "U1") (pin "4") (pinfunction "QB_4") (pintype "output"))
    )
    (net (code "81") (name "unconnected-(U1A-QD-Pad6)") (class "Default")
      (node (ref "U1") (pin "6") (pinfunction "QD_6") (pintype "output"))
    )
    (net (code "82") (name "unconnected-(U1A-QE-Pad10)") (class "Default")
      (node (ref "U1") (pin "10") (pinfunction "QE_10") (pintype "output"))
    )
    (net (code "83") (name "unconnected-(U1A-QF-Pad11)") (class "Default")
      (node (ref "U1") (pin "11") (pinfunction "QF_11") (pintype "output"))
    )
    (net (code "84") (name "unconnected-(U1A-QG-Pad12)") (class "Default")
      (node (ref "U1") (pin "12") (pinfunction "QG_12") (pintype "output"))
    )
    (net (code "85") (name "unconnected-(U2A-QA-Pad3)") (class "Default")
      (node (ref "U2") (pin "3") (pinfunction "QA_3") (pintype "output"))
    )
    (net (code "86") (name "unconnected-(U2A-QB-Pad4)") (class "Default")
      (node (ref "U2") (pin "4") (pinfunction "QB_4") (pintype "output"))
    )
    (net (code "87") (name "unconnected-(U2A-QC-Pad5)") (class "Default")
      (node (ref "U2") (pin "5") (pinfunction "QC_5") (pintype "output"))
    )
    (net (code "88") (name "unconnected-(U2A-QD-Pad6)") (class "Default")
      (node (ref "U2") (pin "6") (pinfunction "QD_6") (pintype "output"))
    )
    (net (code "89") (name "unconnected-(U2A-QF-Pad11)") (class "Default")
      (node (ref "U2") (pin "11") (pinfunction "QF_11") (pintype "output"))
    )
    (net (code "90") (name "unconnected-(U2A-QG-Pad12)") (class "Default")
      (node (ref "U2") (pin "12") (pinfunction "QG_12") (pintype "output"))
    )
    (net (code "91") (name "unconnected-(U2A-QH-Pad13)") (class "Default")
      (node (ref "U2") (pin "13") (pinfunction "QH_13") (pintype "output"))
    )
    (net (code "92") (name "unconnected-(U3A-~{QH}-Pad7)") (class "Default")
      (node (ref "U3") (pin "7") (pinfunction "~{QH}_7") (pintype "output"))
    )
  )
)
